# optiMice_brkV2.net
KiCad netlist of a schematic drawn in EAGLE
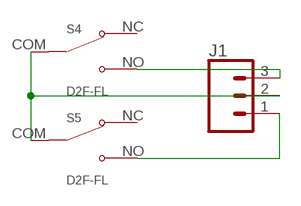
[diagram p0: schematic, sheet 1]

(export (version "E")
  (design (tool "Eeschema 10.0.6"))
  (components
    (comp (ref "J1")
      (value "CONN_03JST-PTH-VERT")
      (footprint "eagle-import:JST-3-PTH-VERT")
      (libsource (lib "eagle-import") (part "CONN_03JST-PTH-VERT"))
    )
    (comp (ref "S4")
      (value "D2F-FL")
      (footprint "eagle-import:SW_D2F-FL")
      (fields (field (name "MF") "Omron Electronics"))
      (libsource (lib "eagle-import") (part "D2F-FL"))
    )
    (comp (ref "S5")
      (value "D2F-FL")
      (footprint "eagle-import:SW_D2F-FL")
      (fields (field (name "MF") "Omron Electronics"))
      (libsource (lib "eagle-import") (part "D2F-FL"))
    )
  )
  (nets
    (net (code "1") (name "Net-(J1-Pad1)") (class "Default")
      (node (ref "J1") (pin "1") (pinfunction "1_1") (pintype "passive"))
      (node (ref "S5") (pin "NO") (pinfunction "NO_NO") (pintype "passive"))
    )
    (net (code "2") (name "Net-(J1-Pad2)") (class "Default")
      (node (ref "J1") (pin "2") (pinfunction "2_2") (pintype "passive"))
      (node (ref "S4") (pin "COM") (pinfunction "COM_COM") (pintype "passive"))
      (node (ref "S5") (pin "COM") (pinfunction "COM_COM") (pintype "passive"))
    )
    (net (code "3") (name "Net-(J1-Pad3)") (class "Default")
      (node (ref "J1") (pin "3") (pinfunction "3_3") (pintype "passive"))
      (node (ref "S4") (pin "NO") (pinfunction "NO_NO") (pintype "passive"))
    )
    (net (code "4") (name "unconnected-(S4-PadNC)") (class "Default")
      (node (ref "S4") (pin "NC") (pinfunction "NC_NC") (pintype "passive"))
    )
    (net (code "5") (name "unconnected-(S5-PadNC)") (class "Default")
      (node (ref "S5") (pin "NC") (pinfunction "NC_NC") (pintype "passive"))
    )
  )
)
